# Power_supplies.net
KiCad netlist of a schematic drawn in Altium Designer
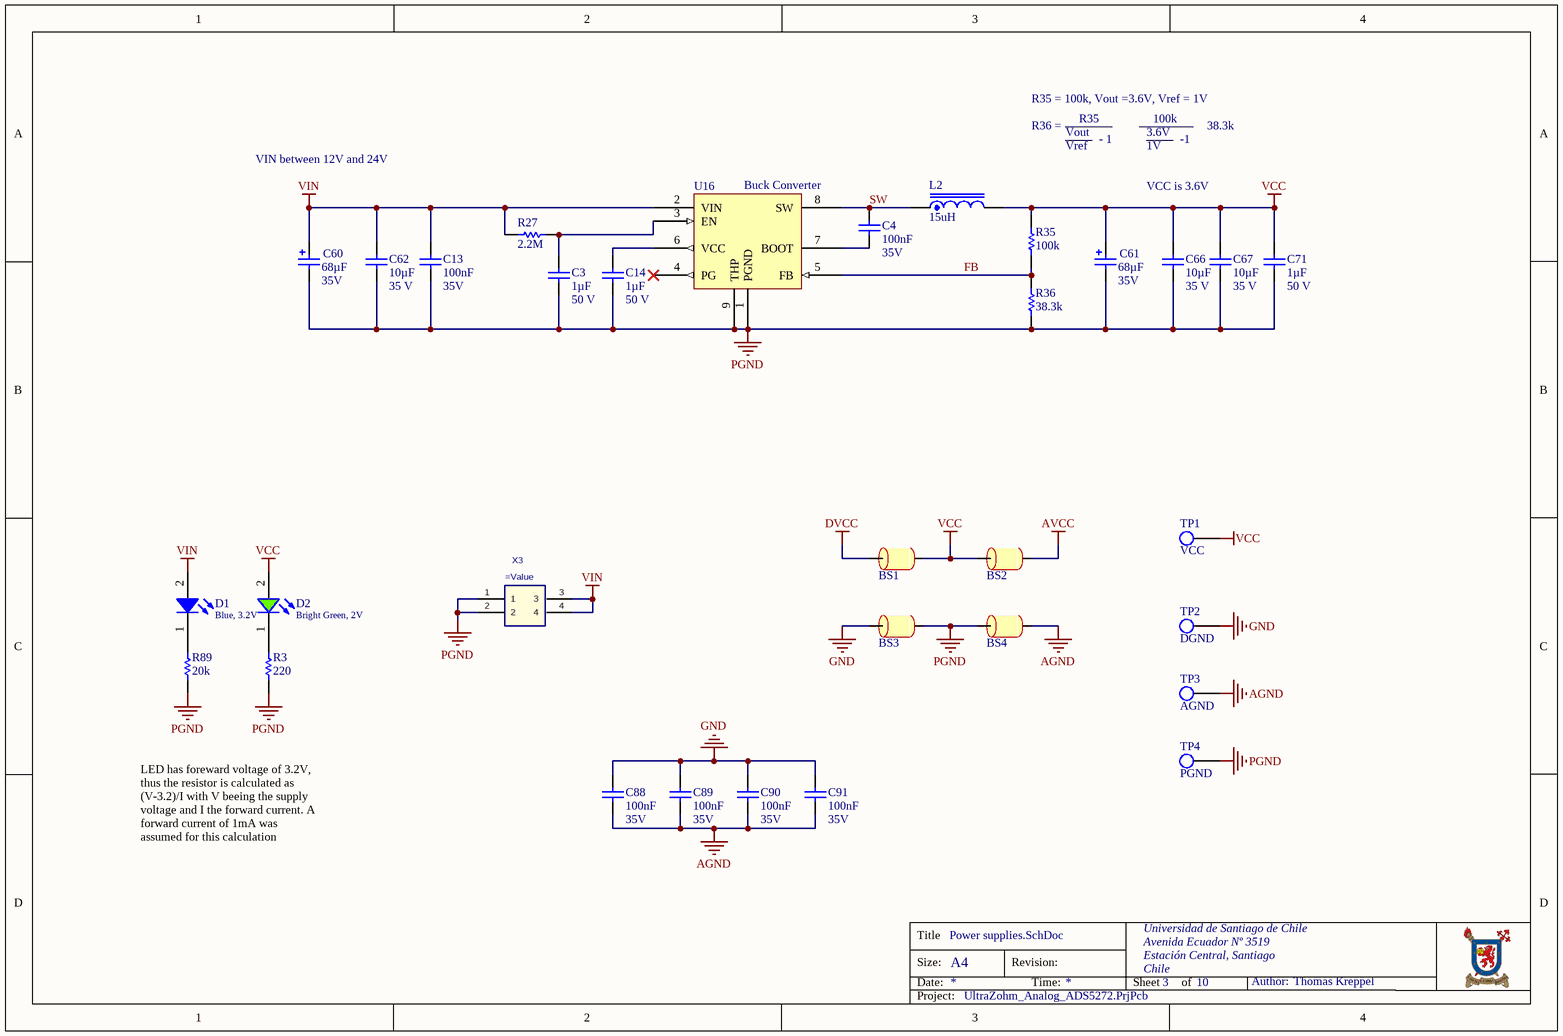
[diagram p0: Power supplies.SchDoc]

(export (version "E")
  (design (tool "Eeschema 10.0.6"))
  (components
    (comp (ref "BS1")
      (value "Ferrite bead")
      (footprint "RES_1206")
      (description "6A")
      (fields (field (name "MPN") "742792121") (field (name "MF") "Würth Elektronik"))
      (libsource (lib "Componentes_SOC") (part "Bead"))
    )
    (comp (ref "BS2")
      (value "Ferrite bead")
      (footprint "RES_1206")
      (description "6A")
      (fields (field (name "MPN") "742792121") (field (name "MF") "Würth Elektronik"))
      (libsource (lib "Componentes_SOC") (part "Bead"))
    )
    (comp (ref "BS3")
      (value "Ferrite bead")
      (footprint "RES_1206")
      (description "6A")
      (fields (field (name "MPN") "742792121") (field (name "MF") "Würth Elektronik"))
      (libsource (lib "Componentes_SOC") (part "Bead"))
    )
    (comp (ref "BS4")
      (value "Ferrite bead")
      (footprint "RES_1206")
      (description "6A")
      (fields (field (name "MPN") "742792121") (field (name "MF") "Würth Elektronik"))
      (libsource (lib "Componentes_SOC") (part "Bead"))
    )
    (comp (ref "C3")
      (value "1µF")
      (footprint "CAP_0603")
      (description "Capacitor Ceramic")
      (fields
        (field (name "MPN") "C0603C105K3RACTU")
        (field (name "VOLTAGE") "50 V")
        (field (name "MF") "KEMET")
      )
      (libsource (lib "Componentes_SOC") (part "Cap_0603"))
    )
    (comp (ref "C4")
      (value "100nF")
      (footprint "CAP_0603")
      (description "Capacitor")
      (fields
        (field (name "MPN") "C0603C104M5RACTU")
        (field (name "MF") "KEMET")
        (field (name "VOLTAGE") "35V")
        (field (name "PUBLISHER") "Altium Limited")
      )
      (libsource (lib "Componentes_SOC") (part "Cap_0603"))
    )
    (comp (ref "C13")
      (value "100nF")
      (footprint "CAP_0603")
      (description "Capacitor")
      (fields
        (field (name "MPN") "C0603C104M5RACTU")
        (field (name "MF") "KEMET")
        (field (name "VOLTAGE") "35V")
        (field (name "PUBLISHER") "Altium Limited")
      )
      (libsource (lib "Componentes_SOC") (part "Cap_0603"))
    )
    (comp (ref "C14")
      (value "1µF")
      (footprint "CAP_0603")
      (description "Capacitor Ceramic")
      (fields
        (field (name "MPN") "C0603C105K3RACTU")
        (field (name "VOLTAGE") "50 V")
        (field (name "MF") "KEMET")
      )
      (libsource (lib "Componentes_SOC") (part "Cap_0603"))
    )
    (comp (ref "C60")
      (value "68µF")
      (footprint "WCAP-ATG8_6.3x11")
      (description "WCAP-ATG8 THT Aluminum Electrolytic Capacitors, D6.3mm x L11mm, 68uF, +/-20%, 35VDC")
      (fields
        (field (name "PART NUMBER") "860010573006")
        (field (name "TOLERANCE") "+/-20%")
        (field (name "VOLTAGE") "35V")
        (field (name "PUBLISHER") "Wurth Elektronik")
      )
      (libsource (lib "Componentes_SOC") (part "860010573006"))
    )
    (comp (ref "C61")
      (value "68µF")
      (footprint "WCAP-ATG8_6.3x11")
      (description "WCAP-ATG8 THT Aluminum Electrolytic Capacitors, D6.3mm x L11mm, 68uF, +/-20%, 35VDC")
      (fields
        (field (name "PART NUMBER") "860010573006")
        (field (name "TOLERANCE") "+/-20%")
        (field (name "VOLTAGE") "35V")
        (field (name "PUBLISHER") "Wurth Elektronik")
      )
      (libsource (lib "Componentes_SOC") (part "860010573006"))
    )
    (comp (ref "C62")
      (value "10µF")
      (footprint "RES_1206")
      (description "Capacitor")
      (fields
        (field (name "MPN") "GRM319R6YA106KA12D")
        (field (name "VOLTAGE") "35 V")
        (field (name "TOLERANCE") "10%")
      )
      (libsource (lib "Componentes_SOC") (part "Cap_1206"))
    )
    (comp (ref "C66")
      (value "10µF")
      (footprint "RES_1206")
      (description "Capacitor")
      (fields
        (field (name "MPN") "GRM319R6YA106KA12D")
        (field (name "VOLTAGE") "35 V")
        (field (name "TOLERANCE") "10%")
      )
      (libsource (lib "Componentes_SOC") (part "Cap_1206"))
    )
    (comp (ref "C67")
      (value "10µF")
      (footprint "RES_1206")
      (description "Capacitor")
      (fields
        (field (name "MPN") "GRM319R6YA106KA12D")
        (field (name "VOLTAGE") "35 V")
        (field (name "TOLERANCE") "10%")
      )
      (libsource (lib "Componentes_SOC") (part "Cap_1206"))
    )
    (comp (ref "C71")
      (value "1µF")
      (footprint "CAP_0603")
      (description "Capacitor Ceramic")
      (fields
        (field (name "MPN") "C0603C105K3RACTU")
        (field (name "VOLTAGE") "50 V")
        (field (name "MF") "KEMET")
      )
      (libsource (lib "Componentes_SOC") (part "Cap_0603"))
    )
    (comp (ref "C88")
      (value "100nF")
      (footprint "CAP_0603")
      (description "Capacitor")
      (fields
        (field (name "MPN") "C0603C104M5RACTU")
        (field (name "MF") "KEMET")
        (field (name "VOLTAGE") "35V")
        (field (name "PUBLISHER") "Altium Limited")
      )
      (libsource (lib "Componentes_SOC") (part "Cap_0603"))
    )
    (comp (ref "C89")
      (value "100nF")
      (footprint "CAP_0603")
      (description "Capacitor")
      (fields
        (field (name "MPN") "C0603C104M5RACTU")
        (field (name "MF") "KEMET")
        (field (name "VOLTAGE") "35V")
        (field (name "PUBLISHER") "Altium Limited")
      )
      (libsource (lib "Componentes_SOC") (part "Cap_0603"))
    )
    (comp (ref "C90")
      (value "100nF")
      (footprint "CAP_0603")
      (description "Capacitor")
      (fields
        (field (name "MPN") "C0603C104M5RACTU")
        (field (name "MF") "KEMET")
        (field (name "VOLTAGE") "35V")
        (field (name "PUBLISHER") "Altium Limited")
      )
      (libsource (lib "Componentes_SOC") (part "Cap_0603"))
    )
    (comp (ref "C91")
      (value "100nF")
      (footprint "CAP_0603")
      (description "Capacitor")
      (fields
        (field (name "MPN") "C0603C104M5RACTU")
        (field (name "MF") "KEMET")
        (field (name "VOLTAGE") "35V")
        (field (name "PUBLISHER") "Altium Limited")
      )
      (libsource (lib "Componentes_SOC") (part "Cap_0603"))
    )
    (comp (ref "D1")
      (value "Blue, 3.2V")
      (footprint "WL-SMCW_0603_H=0.7mm")
      (description "WL-SMCW SMT Mono-color Chip LED Waterclear, size 0603, Blue, 3.2V, 140deg")
      (fields (field (name "MPN") "150060BS75000") (field (name "MF") "Wurth Elektronik"))
      (libsource (lib "Componentes_SOC") (part "150060BS75000"))
    )
    (comp (ref "D2")
      (value "Bright Green, 2V")
      (footprint "WL-SMCW_0603_H=0.7mm")
      (description "WL-SMCW SMT Mono-color Chip LED Waterclear, size 0603, Bright Green, 2V, 140deg")
      (fields (field (name "MPN") "150060VS75000") (field (name "MF") "Wurth Elektronik"))
      (libsource (lib "Componentes_SOC") (part "150060VS75000"))
    )
    (comp (ref "L2")
      (value "15uH")
      (footprint "SMT_inductor_1050_Performance")
      (description "SMT power Inductor, 15uH, 40m DRC")
      (fields (field (name "MANUFACTURER") "Murata"))
      (libsource (lib "Componentes_SOC") (part "B82464G4154M"))
    )
    (comp (ref "R3")
      (value "220")
      (footprint "RES_0603")
      (fields (field (name "TOLERANCE") "1%") (field (name "PUBLISHER") "Altium Limited"))
      (libsource (lib "Componentes_SOC") (part "Res0603"))
    )
    (comp (ref "R27")
      (value "2.2M")
      (footprint "RES_0603")
      (fields
        (field (name "MF") "Yageo")
        (field (name "MPN") "RC0603FR-072M2L")
        (field (name "TOLERANCE") "1%")
        (field (name "PUBLISHER") "Altium Limited")
      )
      (libsource (lib "Componentes_SOC") (part "Res0603"))
    )
    (comp (ref "R35")
      (value "100k")
      (footprint "RES_0603")
      (fields
        (field (name "MF") "Yageo")
        (field (name "MPN") "RC0603FR-07100KL")
        (field (name "TOLERANCE") "1%")
        (field (name "PUBLISHER") "Altium Limited")
      )
      (libsource (lib "Componentes_SOC") (part "Res0603"))
    )
    (comp (ref "R36")
      (value "38.3k")
      (footprint "RES_0603")
      (fields (field (name "TOLERANCE") "1%") (field (name "PUBLISHER") "Altium Limited"))
      (libsource (lib "Componentes_SOC") (part "Res0603"))
    )
    (comp (ref "R89")
      (value "20k")
      (footprint "RES_0603")
      (fields (field (name "TOLERANCE") "1%") (field (name "PUBLISHER") "Altium Limited"))
      (libsource (lib "Componentes_SOC") (part "Res0603"))
    )
    (comp (ref "TP1")
      (value "VCC")
      (footprint "TP_1.6mm")
      (description "1.6mm Test Point Keystone")
      (fields
        (field (name "MANUFACTURER") "Keystone Electronics")
        (field (name "MF") "Keystone")
        (field (name "CREATED") "2020_04_Kreppel")
      )
      (libsource (lib "Componentes_SOC") (part "TP"))
    )
    (comp (ref "TP2")
      (value "DGND")
      (footprint "TP_1.6mm")
      (description "1.6mm Test Point Keystone")
      (fields
        (field (name "MANUFACTURER") "Keystone Electronics")
        (field (name "MF") "Keystone")
        (field (name "CREATED") "2020_04_Kreppel")
      )
      (libsource (lib "Componentes_SOC") (part "TP"))
    )
    (comp (ref "TP3")
      (value "AGND")
      (footprint "TP_1.6mm")
      (description "1.6mm Test Point Keystone")
      (fields
        (field (name "MANUFACTURER") "Keystone Electronics")
        (field (name "MF") "Keystone")
        (field (name "CREATED") "2020_04_Kreppel")
      )
      (libsource (lib "Componentes_SOC") (part "TP"))
    )
    (comp (ref "TP4")
      (value "PGND")
      (footprint "TP_1.6mm")
      (description "1.6mm Test Point Keystone")
      (fields
        (field (name "MANUFACTURER") "Keystone Electronics")
        (field (name "MF") "Keystone")
        (field (name "CREATED") "2020_04_Kreppel")
      )
      (libsource (lib "Componentes_SOC") (part "TP"))
    )
    (comp (ref "U16")
      (value "Buck Converter")
      (footprint "SOIC127P600X170_HS-9N")
      (description "3.8V to 36V, 2A synchronous step-down converter")
      (fields (field (name "MANUFACTURER") "Texas Instruments") (field (name "CREATED") "4/20 Kreppel"))
      (libsource (lib "Componentes_SOC") (part "LMR33620A"))
    )
    (comp (ref "X3")
      (value "~")
      (footprint "IPL1-102-01-L-D-K")
      (description "2.54mm Double Row Terminal Assembly, Right-Angled")
      (fields (field (name "MANUFACTURER") "SAMTEC") (field (name "CREATED") "2018_05_02_AGeiger"))
      (libsource (lib "Componentes_SOC") (part "IPL1-102-XX-X-D-X"))
    )
  )
  (nets
    (net (code "1") (name "/FB") (class "Default")
      (node (ref "R35") (pin "1") (pinfunction "1_1") (pintype "passive"))
      (node (ref "R36") (pin "2") (pinfunction "2_2") (pintype "passive"))
      (node (ref "U16") (pin "5") (pinfunction "FB_5") (pintype "input"))
    )
    (net (code "2") (name "/SW") (class "Default")
      (node (ref "C4") (pin "1") (pinfunction "1_1") (pintype "passive"))
      (node (ref "L2") (pin "1") (pinfunction "1_1") (pintype "passive"))
      (node (ref "U16") (pin "8") (pinfunction "SW_8") (pintype "power_in"))
    )
    (net (code "3") (name "AGND") (class "Default")
      (node (ref "BS4") (pin "2") (pintype "passive"))
      (node (ref "C88") (pin "2") (pinfunction "2_2") (pintype "passive"))
      (node (ref "C89") (pin "2") (pinfunction "2_2") (pintype "passive"))
      (node (ref "C90") (pin "2") (pinfunction "2_2") (pintype "passive"))
      (node (ref "C91") (pin "2") (pinfunction "2_2") (pintype "passive"))
      (node (ref "TP3") (pin "1") (pinfunction "1_1") (pintype "passive"))
    )
    (net (code "4") (name "AVCC") (class "Default") (node (ref "BS2") (pin "2") (pintype "passive")))
    (net (code "5") (name "DVCC") (class "Default") (node (ref "BS1") (pin "1") (pintype "passive")))
    (net (code "6") (name "GND") (class "Default")
      (node (ref "BS3") (pin "1") (pintype "passive"))
      (node (ref "C88") (pin "1") (pinfunction "1_1") (pintype "passive"))
      (node (ref "C89") (pin "1") (pinfunction "1_1") (pintype "passive"))
      (node (ref "C90") (pin "1") (pinfunction "1_1") (pintype "passive"))
      (node (ref "C91") (pin "1") (pinfunction "1_1") (pintype "passive"))
      (node (ref "TP2") (pin "1") (pinfunction "1_1") (pintype "passive"))
    )
    (net (code "7") (name "Net-(D1-K)") (class "Default")
      (node (ref "D1") (pin "1") (pinfunction "K_1") (pintype "passive"))
      (node (ref "R89") (pin "1") (pinfunction "1_1") (pintype "passive"))
    )
    (net (code "8") (name "Net-(D2-K)") (class "Default")
      (node (ref "D2") (pin "1") (pinfunction "K_1") (pintype "passive"))
      (node (ref "R3") (pin "2") (pinfunction "2_2") (pintype "passive"))
    )
    (net (code "9") (name "Net-(U16-BOOT)") (class "Default")
      (node (ref "C4") (pin "2") (pinfunction "2_2") (pintype "passive"))
      (node (ref "U16") (pin "7") (pinfunction "BOOT_7") (pintype "power_in"))
    )
    (net (code "10") (name "Net-(U16-EN)") (class "Default")
      (node (ref "C3") (pin "1") (pinfunction "1_1") (pintype "passive"))
      (node (ref "R27") (pin "1") (pinfunction "1_1") (pintype "passive"))
      (node (ref "U16") (pin "3") (pinfunction "EN_3") (pintype "input"))
    )
    (net (code "11") (name "Net-(U16-VCC)") (class "Default")
      (node (ref "C14") (pin "1") (pinfunction "1_1") (pintype "passive"))
      (node (ref "U16") (pin "6") (pinfunction "VCC_6") (pintype "output"))
    )
    (net (code "12") (name "PGND") (class "Default")
      (node (ref "BS3") (pin "2") (pintype "passive"))
      (node (ref "BS4") (pin "1") (pintype "passive"))
      (node (ref "C13") (pin "2") (pinfunction "2_2") (pintype "passive"))
      (node (ref "C14") (pin "2") (pinfunction "2_2") (pintype "passive"))
      (node (ref "C3") (pin "2") (pinfunction "2_2") (pintype "passive"))
      (node (ref "C60") (pin "1") (pinfunction "N_1") (pintype "passive"))
      (node (ref "C61") (pin "1") (pinfunction "N_1") (pintype "passive"))
      (node (ref "C62") (pin "2") (pinfunction "2_2") (pintype "passive"))
      (node (ref "C66") (pin "2") (pinfunction "2_2") (pintype "passive"))
      (node (ref "C67") (pin "2") (pinfunction "2_2") (pintype "passive"))
      (node (ref "C71") (pin "2") (pinfunction "2_2") (pintype "passive"))
      (node (ref "R3") (pin "1") (pinfunction "1_1") (pintype "passive"))
      (node (ref "R36") (pin "1") (pinfunction "1_1") (pintype "passive"))
      (node (ref "R89") (pin "2") (pinfunction "2_2") (pintype "passive"))
      (node (ref "TP4") (pin "1") (pinfunction "1_1") (pintype "passive"))
      (node (ref "U16") (pin "1") (pinfunction "PGND_1") (pintype "power_in"))
      (node (ref "U16") (pin "9") (pinfunction "THP_9") (pintype "passive"))
      (node (ref "X3") (pin "1") (pinfunction "1_1") (pintype "passive"))
      (node (ref "X3") (pin "2") (pinfunction "2_2") (pintype "passive"))
    )
    (net (code "13") (name "VCC") (class "Default")
      (node (ref "BS1") (pin "2") (pintype "passive"))
      (node (ref "BS2") (pin "1") (pintype "passive"))
      (node (ref "C61") (pin "2") (pinfunction "P_2") (pintype "passive"))
      (node (ref "C66") (pin "1") (pinfunction "1_1") (pintype "passive"))
      (node (ref "C67") (pin "1") (pinfunction "1_1") (pintype "passive"))
      (node (ref "C71") (pin "1") (pinfunction "1_1") (pintype "passive"))
      (node (ref "D2") (pin "2") (pinfunction "A_2") (pintype "passive"))
      (node (ref "L2") (pin "2") (pinfunction "2_2") (pintype "passive"))
      (node (ref "R35") (pin "2") (pinfunction "2_2") (pintype "passive"))
      (node (ref "TP1") (pin "1") (pinfunction "1_1") (pintype "passive"))
    )
    (net (code "14") (name "VIN") (class "Default")
      (node (ref "C13") (pin "1") (pinfunction "1_1") (pintype "passive"))
      (node (ref "C60") (pin "2") (pinfunction "P_2") (pintype "passive"))
      (node (ref "C62") (pin "1") (pinfunction "1_1") (pintype "passive"))
      (node (ref "D1") (pin "2") (pinfunction "A_2") (pintype "passive"))
      (node (ref "R27") (pin "2") (pinfunction "2_2") (pintype "passive"))
      (node (ref "U16") (pin "2") (pinfunction "VIN_2") (pintype "power_in"))
      (node (ref "X3") (pin "3") (pinfunction "3_3") (pintype "passive"))
      (node (ref "X3") (pin "4") (pinfunction "4_4") (pintype "passive"))
    )
    (net (code "15") (name "unconnected-(U16-PG-Pad4)") (class "Default")
      (node (ref "U16") (pin "4") (pinfunction "PG_4") (pintype "output+no_connect"))
    )
  )
)
